# lesson10.net
KiCad netlist of a schematic drawn in Altium Designer
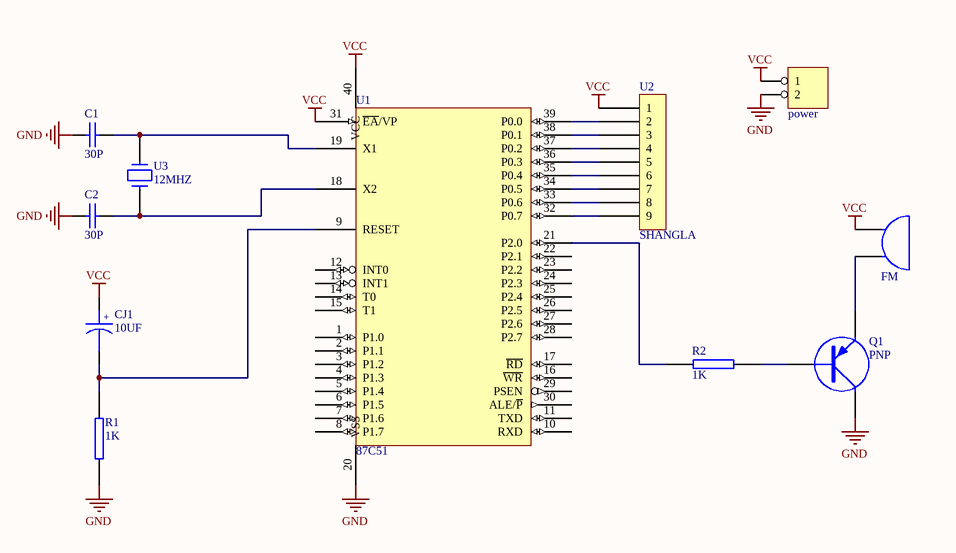
[diagram p0: lesson10.SchDoc]

(export (version "E")
  (design (tool "Eeschema 10.0.6"))
  (components
    (comp (ref "C1")
      (value "30P")
      (footprint "0805")
      (description "Capacitor")
      (libsource (lib "TX-2B") (part "CAP"))
    )
    (comp (ref "C2")
      (value "30P")
      (footprint "0805")
      (description "Capacitor")
      (libsource (lib "TX-2B") (part "CAP"))
    )
    (comp (ref "CJ1")
      (value "10UF")
      (footprint "CD4")
      (description "Capacitor")
      (libsource (lib "TX-2B") (part "CAPACITOR POL"))
    )
    (comp (ref "FM")
      (value "BUZZER")
      (footprint "LB2")
      (description "Buzzer")
      (libsource (lib "TX-2A") (part "BUZZER"))
    )
    (comp (ref "power") (value "P2") (footprint "HDR1X2") (libsource (lib "TX-2A") (part "HEADER 2")))
    (comp (ref "Q1")
      (value "PNP")
      (footprint "SOT-23")
      (description "PNP Transistor")
      (libsource (lib "TX-2A") (part "PNP"))
    )
    (comp (ref "R1") (value "1K") (footprint "0805") (libsource (lib "TX-2B") (part "RES2")))
    (comp (ref "R2") (value "1K") (footprint "0805") (libsource (lib "TX-2B") (part "RES2")))
    (comp (ref "U1") (value "87C51") (footprint "DIP40") (libsource (lib "单片机") (part "87C51")))
    (comp (ref "U2") (value "SHANGLA") (footprint "shangla") (libsource (lib "lesson10") (part "SHANGLA")))
    (comp (ref "U3")
      (value "12MHZ")
      (footprint "JZ")
      (description "Crystal")
      (libsource (lib "TX-2B") (part "CRYSTAL"))
    )
  )
  (nets
    (net (code "1") (name "GND") (class "Default")
      (node (ref "C1") (pin "2") (pinfunction "2_2") (pintype "passive"))
      (node (ref "C2") (pin "2") (pinfunction "2_2") (pintype "passive"))
      (node (ref "Q1") (pin "2") (pinfunction "2_2") (pintype "passive"))
      (node (ref "R1") (pin "1") (pinfunction "1_1") (pintype "passive"))
      (node (ref "U1") (pin "20") (pinfunction "VSS_20") (pintype "power_in"))
      (node (ref "power") (pin "2") (pinfunction "2_2") (pintype "passive"))
    )
    (net (code "2") (name "Net-(FM-B)") (class "Default")
      (node (ref "FM") (pin "2") (pinfunction "B_2") (pintype "passive"))
      (node (ref "Q1") (pin "3") (pinfunction "3_3") (pintype "passive"))
    )
    (net (code "3") (name "Net-(Q1-Pad1)") (class "Default")
      (node (ref "Q1") (pin "1") (pinfunction "1_1") (pintype "passive"))
      (node (ref "R2") (pin "2") (pinfunction "2_2") (pintype "passive"))
    )
    (net (code "4") (name "Net-(U1-P0.0)") (class "Default")
      (node (ref "U1") (pin "39") (pinfunction "P0.0_39") (pintype "bidirectional"))
      (node (ref "U2") (pin "2") (pinfunction "2_2") (pintype "passive"))
    )
    (net (code "5") (name "Net-(U1-P0.1)") (class "Default")
      (node (ref "U1") (pin "38") (pinfunction "P0.1_38") (pintype "bidirectional"))
      (node (ref "U2") (pin "3") (pinfunction "3_3") (pintype "passive"))
    )
    (net (code "6") (name "Net-(U1-P0.2)") (class "Default")
      (node (ref "U1") (pin "37") (pinfunction "P0.2_37") (pintype "bidirectional"))
      (node (ref "U2") (pin "4") (pinfunction "4_4") (pintype "passive"))
    )
    (net (code "7") (name "Net-(U1-P0.3)") (class "Default")
      (node (ref "U1") (pin "36") (pinfunction "P0.3_36") (pintype "bidirectional"))
      (node (ref "U2") (pin "5") (pinfunction "5_5") (pintype "passive"))
    )
    (net (code "8") (name "Net-(U1-P0.4)") (class "Default")
      (node (ref "U1") (pin "35") (pinfunction "P0.4_35") (pintype "bidirectional"))
      (node (ref "U2") (pin "6") (pinfunction "6_6") (pintype "passive"))
    )
    (net (code "9") (name "Net-(U1-P0.5)") (class "Default")
      (node (ref "U1") (pin "34") (pinfunction "P0.5_34") (pintype "bidirectional"))
      (node (ref "U2") (pin "7") (pinfunction "7_7") (pintype "passive"))
    )
    (net (code "10") (name "Net-(U1-P0.6)") (class "Default")
      (node (ref "U1") (pin "33") (pinfunction "P0.6_33") (pintype "bidirectional"))
      (node (ref "U2") (pin "8") (pinfunction "8_8") (pintype "passive"))
    )
    (net (code "11") (name "Net-(U1-P0.7)") (class "Default")
      (node (ref "U1") (pin "32") (pinfunction "P0.7_32") (pintype "bidirectional"))
      (node (ref "U2") (pin "9") (pinfunction "9_9") (pintype "passive"))
    )
    (net (code "12") (name "Net-(U1-P2.0)") (class "Default")
      (node (ref "R2") (pin "1") (pinfunction "1_1") (pintype "passive"))
      (node (ref "U1") (pin "21") (pinfunction "P2.0_21") (pintype "bidirectional"))
    )
    (net (code "13") (name "Net-(U1-RESET)") (class "Default")
      (node (ref "CJ1") (pin "2") (pinfunction "2_2") (pintype "passive"))
      (node (ref "R1") (pin "2") (pinfunction "2_2") (pintype "passive"))
      (node (ref "U1") (pin "9") (pinfunction "RESET_9") (pintype "passive"))
    )
    (net (code "14") (name "Net-(U1-X1)") (class "Default")
      (node (ref "C1") (pin "1") (pinfunction "1_1") (pintype "passive"))
      (node (ref "U1") (pin "19") (pinfunction "X1_19") (pintype "passive"))
      (node (ref "U3") (pin "2") (pinfunction "2_2") (pintype "passive"))
    )
    (net (code "15") (name "Net-(U1-X2)") (class "Default")
      (node (ref "C2") (pin "1") (pinfunction "1_1") (pintype "passive"))
      (node (ref "U1") (pin "18") (pinfunction "X2_18") (pintype "passive"))
      (node (ref "U3") (pin "1") (pinfunction "1_1") (pintype "passive"))
    )
    (net (code "16") (name "VCC") (class "Default")
      (node (ref "CJ1") (pin "1") (pinfunction "1_1") (pintype "passive"))
      (node (ref "FM") (pin "1") (pinfunction "A_1") (pintype "passive"))
      (node (ref "U1") (pin "31") (pinfunction "~{EA}/VP_31") (pintype "input"))
      (node (ref "U1") (pin "40") (pinfunction "VCC_40") (pintype "power_in"))
      (node (ref "U2") (pin "1") (pinfunction "1_1") (pintype "passive"))
      (node (ref "power") (pin "1") (pinfunction "1_1") (pintype "passive"))
    )
    (net (code "17") (name "unconnected-(U1-ALE{slash}~{P}-Pad30)") (class "Default")
      (node (ref "U1") (pin "30") (pinfunction "ALE/~{P}_30") (pintype "output"))
    )
    (net (code "18") (name "unconnected-(U1-INT0-Pad12)") (class "Default")
      (node (ref "U1") (pin "12") (pinfunction "INT0_12") (pintype "bidirectional"))
    )
    (net (code "19") (name "unconnected-(U1-INT1-Pad13)") (class "Default")
      (node (ref "U1") (pin "13") (pinfunction "INT1_13") (pintype "bidirectional"))
    )
    (net (code "20") (name "unconnected-(U1-P1.0-Pad1)") (class "Default")
      (node (ref "U1") (pin "1") (pinfunction "P1.0_1") (pintype "bidirectional"))
    )
    (net (code "21") (name "unconnected-(U1-P1.1-Pad2)") (class "Default")
      (node (ref "U1") (pin "2") (pinfunction "P1.1_2") (pintype "bidirectional"))
    )
    (net (code "22") (name "unconnected-(U1-P1.2-Pad3)") (class "Default")
      (node (ref "U1") (pin "3") (pinfunction "P1.2_3") (pintype "bidirectional"))
    )
    (net (code "23") (name "unconnected-(U1-P1.3-Pad4)") (class "Default")
      (node (ref "U1") (pin "4") (pinfunction "P1.3_4") (pintype "bidirectional"))
    )
    (net (code "24") (name "unconnected-(U1-P1.4-Pad5)") (class "Default")
      (node (ref "U1") (pin "5") (pinfunction "P1.4_5") (pintype "bidirectional"))
    )
    (net (code "25") (name "unconnected-(U1-P1.5-Pad6)") (class "Default")
      (node (ref "U1") (pin "6") (pinfunction "P1.5_6") (pintype "bidirectional"))
    )
    (net (code "26") (name "unconnected-(U1-P1.6-Pad7)") (class "Default")
      (node (ref "U1") (pin "7") (pinfunction "P1.6_7") (pintype "bidirectional"))
    )
    (net (code "27") (name "unconnected-(U1-P1.7-Pad8)") (class "Default")
      (node (ref "U1") (pin "8") (pinfunction "P1.7_8") (pintype "bidirectional"))
    )
    (net (code "28") (name "unconnected-(U1-P2.1-Pad22)") (class "Default")
      (node (ref "U1") (pin "22") (pinfunction "P2.1_22") (pintype "bidirectional"))
    )
    (net (code "29") (name "unconnected-(U1-P2.2-Pad23)") (class "Default")
      (node (ref "U1") (pin "23") (pinfunction "P2.2_23") (pintype "bidirectional"))
    )
    (net (code "30") (name "unconnected-(U1-P2.3-Pad24)") (class "Default")
      (node (ref "U1") (pin "24") (pinfunction "P2.3_24") (pintype "bidirectional"))
    )
    (net (code "31") (name "unconnected-(U1-P2.4-Pad25)") (class "Default")
      (node (ref "U1") (pin "25") (pinfunction "P2.4_25") (pintype "bidirectional"))
    )
    (net (code "32") (name "unconnected-(U1-P2.5-Pad26)") (class "Default")
      (node (ref "U1") (pin "26") (pinfunction "P2.5_26") (pintype "bidirectional"))
    )
    (net (code "33") (name "unconnected-(U1-P2.6-Pad27)") (class "Default")
      (node (ref "U1") (pin "27") (pinfunction "P2.6_27") (pintype "bidirectional"))
    )
    (net (code "34") (name "unconnected-(U1-P2.7-Pad28)") (class "Default")
      (node (ref "U1") (pin "28") (pinfunction "P2.7_28") (pintype "bidirectional"))
    )
    (net (code "35") (name "unconnected-(U1-PSEN-Pad29)") (class "Default")
      (node (ref "U1") (pin "29") (pinfunction "PSEN_29") (pintype "output"))
    )
    (net (code "36") (name "unconnected-(U1-RXD-Pad10)") (class "Default")
      (node (ref "U1") (pin "10") (pinfunction "RXD_10") (pintype "bidirectional"))
    )
    (net (code "37") (name "unconnected-(U1-T0-Pad14)") (class "Default")
      (node (ref "U1") (pin "14") (pinfunction "T0_14") (pintype "bidirectional"))
    )
    (net (code "38") (name "unconnected-(U1-T1-Pad15)") (class "Default")
      (node (ref "U1") (pin "15") (pinfunction "T1_15") (pintype "bidirectional"))
    )
    (net (code "39") (name "unconnected-(U1-TXD-Pad11)") (class "Default")
      (node (ref "U1") (pin "11") (pinfunction "TXD_11") (pintype "bidirectional"))
    )
    (net (code "40") (name "unconnected-(U1-~{RD}-Pad17)") (class "Default")
      (node (ref "U1") (pin "17") (pinfunction "~{RD}_17") (pintype "bidirectional"))
    )
    (net (code "41") (name "unconnected-(U1-~{WR}-Pad16)") (class "Default")
      (node (ref "U1") (pin "16") (pinfunction "~{WR}_16") (pintype "bidirectional"))
    )
  )
)
